# RH021_2.net
KiCad netlist of a schematic drawn in EAGLE
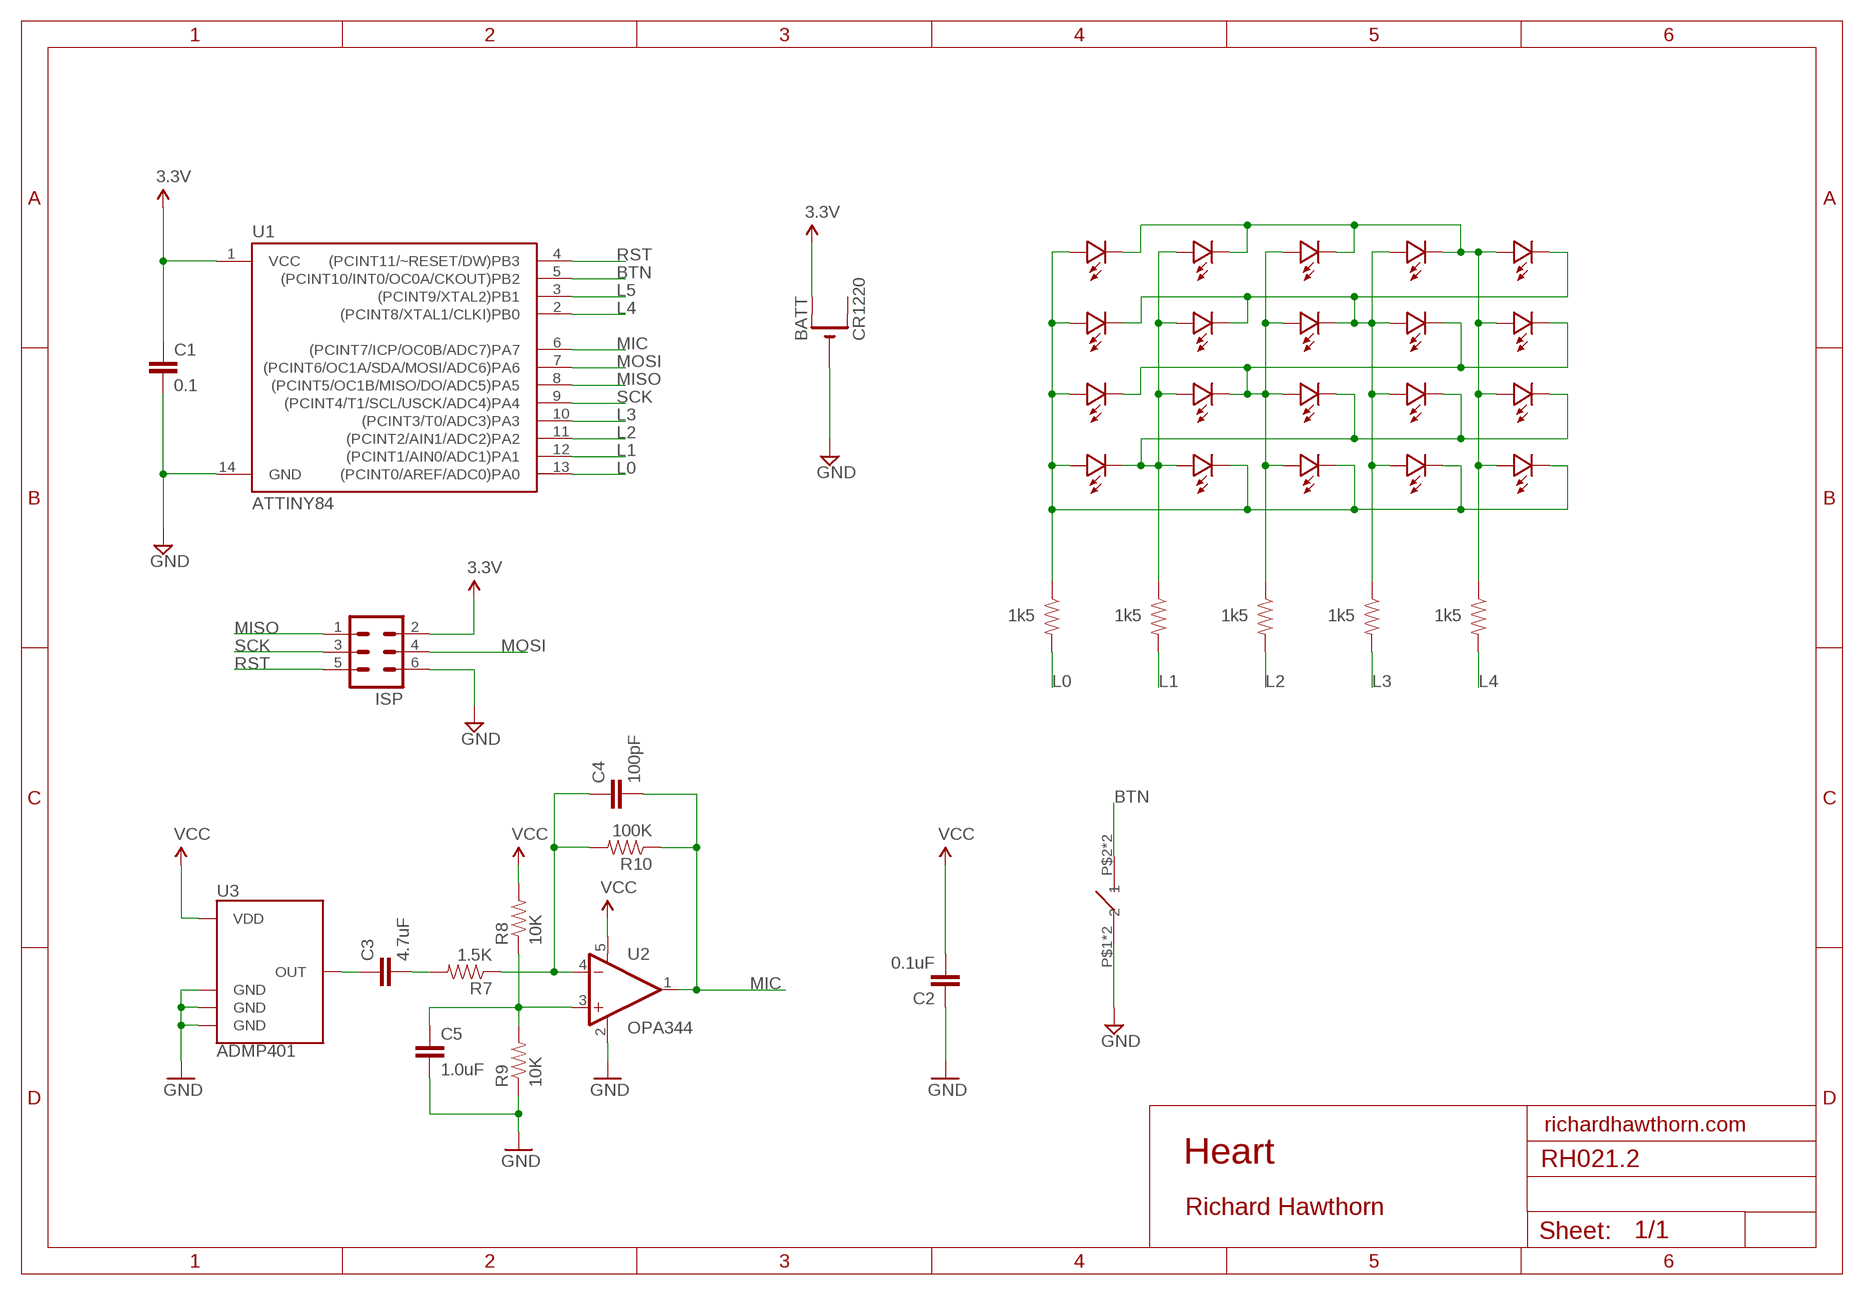
[diagram p0: schematic, sheet 1]

(export (version "E")
  (design (tool "Eeschema 10.0.6"))
  (components
    (comp (ref "BATT")
      (value "CR1220")
      (footprint "eagle-import:CR1220-SMD")
      (libsource (lib "eagle-import") (part "CR1220SMT"))
    )
    (comp (ref "BTN1")
      (value "TURTLE-3PIN")
      (footprint "eagle-import:TURTLE-3PIN")
      (libsource (lib "eagle-import") (part "TURTLE-3PIN"))
    )
    (comp (ref "C1")
      (value "0.1")
      (footprint "eagle-import:0603-CAP")
      (libsource (lib "eagle-import") (part "CAP0603-CAP"))
    )
    (comp (ref "C2")
      (value "0.1uF")
      (footprint "eagle-import:0402-CAP")
      (libsource (lib "eagle-import") (part "SparkFun_CAP0402-CAP"))
    )
    (comp (ref "C3")
      (value "4.7uF")
      (footprint "eagle-import:0402-CAP")
      (libsource (lib "eagle-import") (part "SparkFun_CAP0402-CAP"))
    )
    (comp (ref "C4")
      (value "100pF")
      (footprint "eagle-import:0402-CAP")
      (libsource (lib "eagle-import") (part "SparkFun_CAP0402-CAP"))
    )
    (comp (ref "C5")
      (value "1.0uF")
      (footprint "eagle-import:0402-CAP")
      (libsource (lib "eagle-import") (part "SparkFun_CAP0402-CAP"))
    )
    (comp (ref "ISP")
      (value "MA03-2")
      (footprint "eagle-import:MA03-2")
      (libsource (lib "eagle-import") (part "MA03-2"))
    )
    (comp (ref "LED1")
      (value "LED0603")
      (footprint "eagle-import:0603-LED")
      (libsource (lib "eagle-import") (part "LED0603"))
    )
    (comp (ref "LED2")
      (value "LED0603")
      (footprint "eagle-import:0603-LED")
      (libsource (lib "eagle-import") (part "LED0603"))
    )
    (comp (ref "LED3")
      (value "LED0603")
      (footprint "eagle-import:0603-LED")
      (libsource (lib "eagle-import") (part "LED0603"))
    )
    (comp (ref "LED4")
      (value "LED0603")
      (footprint "eagle-import:0603-LED")
      (libsource (lib "eagle-import") (part "LED0603"))
    )
    (comp (ref "LED5")
      (value "LED0603")
      (footprint "eagle-import:0603-LED")
      (libsource (lib "eagle-import") (part "LED0603"))
    )
    (comp (ref "LED6")
      (value "LED0603")
      (footprint "eagle-import:0603-LED")
      (libsource (lib "eagle-import") (part "LED0603"))
    )
    (comp (ref "LED7")
      (value "LED0603")
      (footprint "eagle-import:0603-LED")
      (libsource (lib "eagle-import") (part "LED0603"))
    )
    (comp (ref "LED8")
      (value "LED0603")
      (footprint "eagle-import:0603-LED")
      (libsource (lib "eagle-import") (part "LED0603"))
    )
    (comp (ref "LED9")
      (value "LED0603")
      (footprint "eagle-import:0603-LED")
      (libsource (lib "eagle-import") (part "LED0603"))
    )
    (comp (ref "LED10")
      (value "LED0603")
      (footprint "eagle-import:0603-LED")
      (libsource (lib "eagle-import") (part "LED0603"))
    )
    (comp (ref "LED11")
      (value "LED0603")
      (footprint "eagle-import:0603-LED")
      (libsource (lib "eagle-import") (part "LED0603"))
    )
    (comp (ref "LED12")
      (value "LED0603")
      (footprint "eagle-import:0603-LED")
      (libsource (lib "eagle-import") (part "LED0603"))
    )
    (comp (ref "LED13")
      (value "LED0603")
      (footprint "eagle-import:0603-LED")
      (libsource (lib "eagle-import") (part "LED0603"))
    )
    (comp (ref "LED14")
      (value "LED0603")
      (footprint "eagle-import:0603-LED")
      (libsource (lib "eagle-import") (part "LED0603"))
    )
    (comp (ref "LED15")
      (value "LED0603")
      (footprint "eagle-import:0603-LED")
      (libsource (lib "eagle-import") (part "LED0603"))
    )
    (comp (ref "LED16")
      (value "LED0603")
      (footprint "eagle-import:0603-LED")
      (libsource (lib "eagle-import") (part "LED0603"))
    )
    (comp (ref "LED17")
      (value "LED0603")
      (footprint "eagle-import:0603-LED")
      (libsource (lib "eagle-import") (part "LED0603"))
    )
    (comp (ref "LED18")
      (value "LED0603")
      (footprint "eagle-import:0603-LED")
      (libsource (lib "eagle-import") (part "LED0603"))
    )
    (comp (ref "LED19")
      (value "LED0603")
      (footprint "eagle-import:0603-LED")
      (libsource (lib "eagle-import") (part "LED0603"))
    )
    (comp (ref "LED20")
      (value "LED0603")
      (footprint "eagle-import:0603-LED")
      (libsource (lib "eagle-import") (part "LED0603"))
    )
    (comp (ref "R1")
      (value "1k5")
      (footprint "eagle-import:0603-RES")
      (libsource (lib "eagle-import") (part "RESISTOR0603-RES"))
    )
    (comp (ref "R2")
      (value "1k5")
      (footprint "eagle-import:0603-RES")
      (libsource (lib "eagle-import") (part "RESISTOR0603-RES"))
    )
    (comp (ref "R3")
      (value "1k5")
      (footprint "eagle-import:0603-RES")
      (libsource (lib "eagle-import") (part "RESISTOR0603-RES"))
    )
    (comp (ref "R4")
      (value "1k5")
      (footprint "eagle-import:0603-RES")
      (libsource (lib "eagle-import") (part "RESISTOR0603-RES"))
    )
    (comp (ref "R5")
      (value "1k5")
      (footprint "eagle-import:0603-RES")
      (libsource (lib "eagle-import") (part "RESISTOR0603-RES"))
    )
    (comp (ref "R7")
      (value "1.5K")
      (footprint "eagle-import:0402-RES")
      (libsource (lib "eagle-import") (part "SparkFun_RESISTOR0402-RES"))
    )
    (comp (ref "R8")
      (value "10K")
      (footprint "eagle-import:0402-RES")
      (libsource (lib "eagle-import") (part "SparkFun_RESISTOR0402-RES"))
    )
    (comp (ref "R9")
      (value "10K")
      (footprint "eagle-import:0402-RES")
      (libsource (lib "eagle-import") (part "SparkFun_RESISTOR0402-RES"))
    )
    (comp (ref "R10")
      (value "100K")
      (footprint "eagle-import:0402-RES")
      (libsource (lib "eagle-import") (part "SparkFun_RESISTOR0402-RES"))
    )
    (comp (ref "U1")
      (value "ATTINY84")
      (footprint "eagle-import:SO14")
      (libsource (lib "eagle-import") (part "ATTINY84"))
    )
    (comp (ref "U2")
      (value "OPA344")
      (footprint "eagle-import:SOT23-5")
      (libsource (lib "eagle-import") (part "OPA344"))
    )
    (comp (ref "U3")
      (value "ADMP401")
      (footprint "eagle-import:ADMP401")
      (libsource (lib "eagle-import") (part "ADMP401"))
    )
  )
  (nets
    (net (code "1") (name "/BTN") (class "Default")
      (node (ref "BTN1") (pin "P$2") (pinfunction "2_P$2") (pintype "bidirectional"))
      (node (ref "BTN1") (pin "P$4") (pinfunction "2_P$4") (pintype "bidirectional"))
      (node (ref "U1") (pin "5") (pinfunction "(PCINT10/INT0/OC0A/CKOUT)PB2_5") (pintype "bidirectional"))
    )
    (net (code "2") (name "/L0") (class "Default")
      (node (ref "R1") (pin "2") (pinfunction "2_2") (pintype "passive"))
      (node (ref "U1") (pin "13") (pinfunction "(PCINT0/AREF/ADC0)PA0_13") (pintype "bidirectional"))
    )
    (net (code "3") (name "/L1") (class "Default")
      (node (ref "R2") (pin "2") (pinfunction "2_2") (pintype "passive"))
      (node (ref "U1") (pin "12") (pinfunction "(PCINT1/AIN0/ADC1)PA1_12") (pintype "bidirectional"))
    )
    (net (code "4") (name "/L2") (class "Default")
      (node (ref "R3") (pin "2") (pinfunction "2_2") (pintype "passive"))
      (node (ref "U1") (pin "11") (pinfunction "(PCINT2/AIN1/ADC2)PA2_11") (pintype "bidirectional"))
    )
    (net (code "5") (name "/L3") (class "Default")
      (node (ref "R4") (pin "2") (pinfunction "2_2") (pintype "passive"))
      (node (ref "U1") (pin "10") (pinfunction "(PCINT3/T0/ADC3)PA3_10") (pintype "bidirectional"))
    )
    (net (code "6") (name "/L4") (class "Default")
      (node (ref "R5") (pin "2") (pinfunction "2_2") (pintype "passive"))
      (node (ref "U1") (pin "2") (pinfunction "(PCINT8/XTAL1/CLKI)PB0_2") (pintype "bidirectional"))
    )
    (net (code "7") (name "/L5") (class "Default")
      (node (ref "U1") (pin "3") (pinfunction "(PCINT9/XTAL2)PB1_3") (pintype "bidirectional"))
    )
    (net (code "8") (name "/MIC") (class "Default")
      (node (ref "C4") (pin "2") (pinfunction "2_2") (pintype "passive"))
      (node (ref "R10") (pin "1") (pinfunction "1_1") (pintype "passive"))
      (node (ref "U1") (pin "6") (pinfunction "(PCINT7/ICP/OC0B/ADC7)PA7_6") (pintype "bidirectional"))
      (node (ref "U2") (pin "1") (pinfunction "OUT_1") (pintype "output"))
    )
    (net (code "9") (name "/MISO") (class "Default")
      (node (ref "ISP") (pin "1") (pinfunction "1_1") (pintype "passive"))
      (node (ref "U1") (pin "8") (pinfunction "(PCINT5/OC1B/MISO/DO/ADC5)PA5_8") (pintype "bidirectional"))
    )
    (net (code "10") (name "/MOSI") (class "Default")
      (node (ref "ISP") (pin "4") (pinfunction "4_4") (pintype "passive"))
      (node (ref "U1") (pin "7") (pinfunction "(PCINT6/OC1A/SDA/MOSI/ADC6)PA6_7") (pintype "bidirectional"))
    )
    (net (code "11") (name "/RST") (class "Default")
      (node (ref "ISP") (pin "5") (pinfunction "5_5") (pintype "passive"))
      (node (ref "U1") (pin "4") (pinfunction "(PCINT11/~{RESET/DW})PB3_4") (pintype "bidirectional"))
    )
    (net (code "12") (name "/SCK") (class "Default")
      (node (ref "ISP") (pin "3") (pinfunction "3_3") (pintype "passive"))
      (node (ref "U1") (pin "9") (pinfunction "(PCINT4/T1/SCL/USCK/ADC4)PA4_9") (pintype "bidirectional"))
    )
    (net (code "13") (name "3.3V") (class "Default")
      (node (ref "BATT") (pin "+$1") (pinfunction "+_+$1") (pintype "passive"))
      (node (ref "C1") (pin "1") (pinfunction "1_1") (pintype "passive"))
      (node (ref "C2") (pin "2") (pinfunction "2_2") (pintype "passive"))
      (node (ref "ISP") (pin "2") (pinfunction "2_2") (pintype "passive"))
      (node (ref "R8") (pin "2") (pinfunction "2_2") (pintype "passive"))
      (node (ref "U1") (pin "1") (pinfunction "VCC_1") (pintype "bidirectional"))
      (node (ref "U2") (pin "5") (pinfunction "V+_5") (pintype "power_in"))
      (node (ref "U3") (pin "5") (pinfunction "VDD_5") (pintype "bidirectional"))
    )
    (net (code "14") (name "GND") (class "Default")
      (node (ref "BATT") (pin "-") (pinfunction "-_-") (pintype "passive"))
      (node (ref "BTN1") (pin "P$1") (pinfunction "1_P$1") (pintype "bidirectional"))
      (node (ref "BTN1") (pin "P$3") (pinfunction "1_P$3") (pintype "bidirectional"))
      (node (ref "C1") (pin "2") (pinfunction "2_2") (pintype "passive"))
      (node (ref "C2") (pin "1") (pinfunction "1_1") (pintype "passive"))
      (node (ref "C5") (pin "2") (pinfunction "2_2") (pintype "passive"))
      (node (ref "ISP") (pin "6") (pinfunction "6_6") (pintype "passive"))
      (node (ref "R9") (pin "1") (pinfunction "1_1") (pintype "passive"))
      (node (ref "U1") (pin "14") (pinfunction "GND_14") (pintype "bidirectional"))
      (node (ref "U2") (pin "2") (pinfunction "V-_2") (pintype "power_in"))
      (node (ref "U3") (pin "2") (pinfunction "GND_2") (pintype "bidirectional"))
      (node (ref "U3") (pin "4") (pinfunction "GND_4") (pintype "bidirectional"))
      (node (ref "U3") (pin "6") (pinfunction "GND_6") (pintype "bidirectional"))
    )
    (net (code "15") (name "Net-(C3-Pad2)") (class "Default")
      (node (ref "C3") (pin "2") (pinfunction "2_2") (pintype "passive"))
      (node (ref "R7") (pin "2") (pinfunction "2_2") (pintype "passive"))
    )
    (net (code "16") (name "Net-(LED1-PadMINUS)") (class "Default")
      (node (ref "LED1") (pin "MINUS") (pinfunction "MINUS_MINUS") (pintype "passive"))
      (node (ref "LED10") (pin "PLUS") (pinfunction "PLUS_PLUS") (pintype "passive"))
      (node (ref "LED15") (pin "PLUS") (pinfunction "PLUS_PLUS") (pintype "passive"))
      (node (ref "LED2") (pin "MINUS") (pinfunction "MINUS_MINUS") (pintype "passive"))
      (node (ref "LED20") (pin "PLUS") (pinfunction "PLUS_PLUS") (pintype "passive"))
      (node (ref "LED3") (pin "MINUS") (pinfunction "MINUS_MINUS") (pintype "passive"))
      (node (ref "LED4") (pin "MINUS") (pinfunction "MINUS_MINUS") (pintype "passive"))
      (node (ref "LED5") (pin "PLUS") (pinfunction "PLUS_PLUS") (pintype "passive"))
      (node (ref "R5") (pin "1") (pinfunction "1_1") (pintype "passive"))
    )
    (net (code "17") (name "Net-(LED1-PadPLUS)") (class "Default")
      (node (ref "LED1") (pin "PLUS") (pinfunction "PLUS_PLUS") (pintype "passive"))
      (node (ref "LED11") (pin "PLUS") (pinfunction "PLUS_PLUS") (pintype "passive"))
      (node (ref "LED16") (pin "PLUS") (pinfunction "PLUS_PLUS") (pintype "passive"))
      (node (ref "LED17") (pin "MINUS") (pinfunction "MINUS_MINUS") (pintype "passive"))
      (node (ref "LED18") (pin "MINUS") (pinfunction "MINUS_MINUS") (pintype "passive"))
      (node (ref "LED19") (pin "MINUS") (pinfunction "MINUS_MINUS") (pintype "passive"))
      (node (ref "LED20") (pin "MINUS") (pinfunction "MINUS_MINUS") (pintype "passive"))
      (node (ref "LED6") (pin "PLUS") (pinfunction "PLUS_PLUS") (pintype "passive"))
      (node (ref "R1") (pin "1") (pinfunction "1_1") (pintype "passive"))
    )
    (net (code "18") (name "Net-(LED10-PadMINUS)") (class "Default")
      (node (ref "LED10") (pin "MINUS") (pinfunction "MINUS_MINUS") (pintype "passive"))
      (node (ref "LED11") (pin "MINUS") (pinfunction "MINUS_MINUS") (pintype "passive"))
      (node (ref "LED12") (pin "MINUS") (pinfunction "MINUS_MINUS") (pintype "passive"))
      (node (ref "LED13") (pin "PLUS") (pinfunction "PLUS_PLUS") (pintype "passive"))
      (node (ref "LED18") (pin "PLUS") (pinfunction "PLUS_PLUS") (pintype "passive"))
      (node (ref "LED3") (pin "PLUS") (pinfunction "PLUS_PLUS") (pintype "passive"))
      (node (ref "LED8") (pin "PLUS") (pinfunction "PLUS_PLUS") (pintype "passive"))
      (node (ref "LED9") (pin "MINUS") (pinfunction "MINUS_MINUS") (pintype "passive"))
      (node (ref "R3") (pin "1") (pinfunction "1_1") (pintype "passive"))
    )
    (net (code "19") (name "Net-(LED12-PadPLUS)") (class "Default")
      (node (ref "LED12") (pin "PLUS") (pinfunction "PLUS_PLUS") (pintype "passive"))
      (node (ref "LED13") (pin "MINUS") (pinfunction "MINUS_MINUS") (pintype "passive"))
      (node (ref "LED14") (pin "MINUS") (pinfunction "MINUS_MINUS") (pintype "passive"))
      (node (ref "LED15") (pin "MINUS") (pinfunction "MINUS_MINUS") (pintype "passive"))
      (node (ref "LED16") (pin "MINUS") (pinfunction "MINUS_MINUS") (pintype "passive"))
      (node (ref "LED17") (pin "PLUS") (pinfunction "PLUS_PLUS") (pintype "passive"))
      (node (ref "LED2") (pin "PLUS") (pinfunction "PLUS_PLUS") (pintype "passive"))
      (node (ref "LED7") (pin "PLUS") (pinfunction "PLUS_PLUS") (pintype "passive"))
      (node (ref "R2") (pin "1") (pinfunction "1_1") (pintype "passive"))
    )
    (net (code "20") (name "Net-(LED14-PadPLUS)") (class "Default")
      (node (ref "LED14") (pin "PLUS") (pinfunction "PLUS_PLUS") (pintype "passive"))
      (node (ref "LED19") (pin "PLUS") (pinfunction "PLUS_PLUS") (pintype "passive"))
      (node (ref "LED4") (pin "PLUS") (pinfunction "PLUS_PLUS") (pintype "passive"))
      (node (ref "LED5") (pin "MINUS") (pinfunction "MINUS_MINUS") (pintype "passive"))
      (node (ref "LED6") (pin "MINUS") (pinfunction "MINUS_MINUS") (pintype "passive"))
      (node (ref "LED7") (pin "MINUS") (pinfunction "MINUS_MINUS") (pintype "passive"))
      (node (ref "LED8") (pin "MINUS") (pinfunction "MINUS_MINUS") (pintype "passive"))
      (node (ref "LED9") (pin "PLUS") (pinfunction "PLUS_PLUS") (pintype "passive"))
      (node (ref "R4") (pin "1") (pinfunction "1_1") (pintype "passive"))
    )
    (net (code "21") (name "Net-(U2-+IN)") (class "Default")
      (node (ref "C5") (pin "1") (pinfunction "1_1") (pintype "passive"))
      (node (ref "R8") (pin "1") (pinfunction "1_1") (pintype "passive"))
      (node (ref "R9") (pin "2") (pinfunction "2_2") (pintype "passive"))
      (node (ref "U2") (pin "3") (pinfunction "+IN_3") (pintype "input"))
    )
    (net (code "22") (name "Net-(U2--IN)") (class "Default")
      (node (ref "C4") (pin "1") (pinfunction "1_1") (pintype "passive"))
      (node (ref "R10") (pin "2") (pinfunction "2_2") (pintype "passive"))
      (node (ref "R7") (pin "1") (pinfunction "1_1") (pintype "passive"))
      (node (ref "U2") (pin "4") (pinfunction "-IN_4") (pintype "input"))
    )
    (net (code "23") (name "Net-(U3-OUT)") (class "Default")
      (node (ref "C3") (pin "1") (pinfunction "1_1") (pintype "passive"))
      (node (ref "U3") (pin "1") (pinfunction "OUT_1") (pintype "bidirectional"))
    )
    (net (code "24") (name "unconnected-(BATT-+1-Pad+$2)") (class "Default")
      (node (ref "BATT") (pin "+$2") (pinfunction "+1_+$2") (pintype "passive"))
    )
  )
)
